# STC.net
KiCad netlist of a schematic drawn in Altium Designer
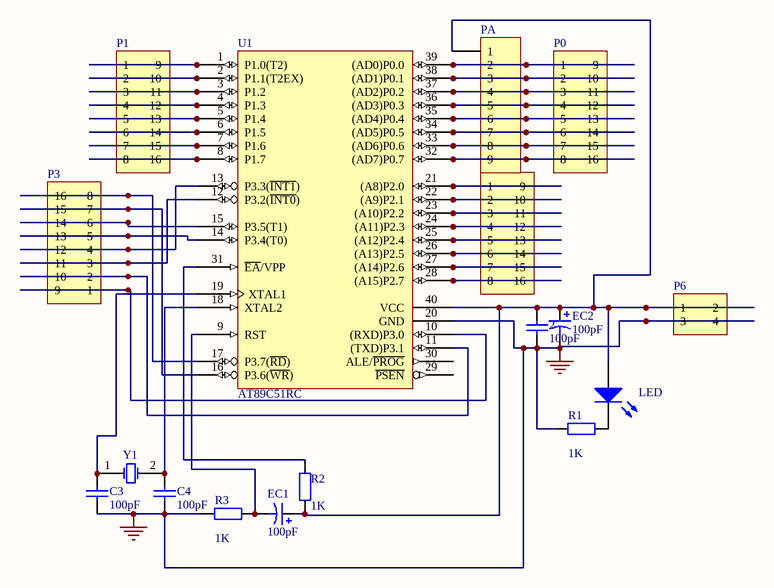
[diagram p0: STC最小系统板.SCHDOC]

(export (version "E")
  (design (tool "Eeschema 10.0.6"))
  (components
    (comp (ref "2")
      (value "100pF")
      (footprint "CAPR5-4X5")
      (description "Capacitor (Semiconductor SIM Model)")
      (fields (field (name "Comment") "Cap Semi") (field (name "PUBLISHER") "Altium Limited"))
      (libsource (lib "Miscellaneous Devices") (part "Cap Semi"))
    )
    (comp (ref "C3")
      (value "100pF")
      (footprint "CAPR5-4X5")
      (description "Capacitor (Semiconductor SIM Model)")
      (fields (field (name "Comment") "Cap Semi") (field (name "PUBLISHER") "Altium Limited"))
      (libsource (lib "Miscellaneous Devices") (part "Cap Semi"))
    )
    (comp (ref "C4")
      (value "100pF")
      (footprint "CAPR5-4X5")
      (description "Capacitor (Semiconductor SIM Model)")
      (fields (field (name "Comment") "Cap Semi") (field (name "PUBLISHER") "Altium Limited"))
      (libsource (lib "Miscellaneous Devices") (part "Cap Semi"))
    )
    (comp (ref "EC1")
      (value "100pF")
      (footprint "CAPPR1.5-4x5")
      (description "Polarized Capacitor (Radial)")
      (fields (field (name "Comment") "Cap Pol1") (field (name "PUBLISHER") "Altium Limited"))
      (libsource (lib "Miscellaneous Devices") (part "Cap Pol1"))
    )
    (comp (ref "EC2")
      (value "100pF")
      (footprint "CAPPR1.5-4x5")
      (description "Polarized Capacitor (Radial)")
      (fields (field (name "Comment") "Cap Pol1") (field (name "PUBLISHER") "Altium Limited"))
      (libsource (lib "Miscellaneous Devices") (part "Cap Pol1"))
    )
    (comp (ref "LED")
      (value "LED0")
      (footprint "CAPPR1.27-1.7x2.8")
      (description "Typical INFRARED GaAs LED")
      (fields (field (name "PUBLISHER") "Altium Limited"))
      (libsource (lib "Miscellaneous Devices") (part "LED0"))
    )
    (comp (ref "P0")
      (value "Header 8X2A")
      (footprint "HDR2X8_CEN")
      (description "Header, 8-Pin, Dual row")
      (fields (field (name "PUBLISHER") "Altium Limited"))
      (libsource (lib "Miscellaneous Connectors") (part "Header 8X2A"))
    )
    (comp (ref "P1")
      (value "Header 8X2A")
      (footprint "HDR2X8_CEN")
      (description "Header, 8-Pin, Dual row")
      (fields (field (name "PUBLISHER") "Altium Limited"))
      (libsource (lib "Miscellaneous Connectors") (part "Header 8X2A"))
    )
    (comp (ref "P2")
      (value "Header 8X2A")
      (footprint "HDR2X8_CEN")
      (description "Header, 8-Pin, Dual row")
      (fields (field (name "PUBLISHER") "Altium Limited"))
      (libsource (lib "Miscellaneous Connectors") (part "Header 8X2A"))
    )
    (comp (ref "P3")
      (value "Header 8X2A")
      (footprint "HDR2X8_CEN")
      (description "Header, 8-Pin, Dual row")
      (fields (field (name "PUBLISHER") "Altium Limited"))
      (libsource (lib "") (part "Header 8X2A_1"))
    )
    (comp (ref "P6")
      (value "MHDR2X2")
      (footprint "MHDR2X2")
      (description "Header, 2-Pin, Dual row")
      (fields (field (name "PUBLISHER") "Altium Limited"))
      (libsource (lib "Miscellaneous Connectors") (part "MHDR2X2"))
    )
    (comp (ref "PA")
      (value "Header 9")
      (footprint "HDR1X9")
      (description "Header, 9-Pin")
      (fields (field (name "PUBLISHER") "Altium Limited"))
      (libsource (lib "Miscellaneous Connectors") (part "Header 9"))
    )
    (comp (ref "R1")
      (value "1K")
      (footprint "AXIAL-0.4")
      (description "Resistor")
      (fields (field (name "Comment") "Res2") (field (name "PUBLISHER") "Altium Limited"))
      (libsource (lib "Miscellaneous Devices") (part "Res2"))
    )
    (comp (ref "R2")
      (value "1K")
      (footprint "AXIAL-0.4")
      (description "Resistor")
      (fields (field (name "Comment") "Res2") (field (name "PUBLISHER") "Altium Limited"))
      (libsource (lib "") (part "Res2_1"))
    )
    (comp (ref "R3")
      (value "1K")
      (footprint "AXIAL-0.4")
      (description "Resistor")
      (fields (field (name "Comment") "Res2") (field (name "PUBLISHER") "Altium Limited"))
      (libsource (lib "Miscellaneous Devices") (part "Res2"))
    )
    (comp (ref "U1")
      (value "AT89C51RC")
      (footprint "DIP-40")
      (description "8-Bit Microcontroller with 32K Flash ROM")
      (libsource (lib "Atmel Microcontroller 8051 Architecture") (part "AT89C51RC"))
    )
    (comp (ref "Y1")
      (value "XTAL")
      (footprint "RAD-0.2")
      (description "Crystal Oscillator")
      (fields (field (name "PUBLISHER") "Altium Limited"))
      (libsource (lib "Miscellaneous Devices") (part "XTAL"))
    )
  )
  (nets
    (net (code "1") (name "GND") (class "Default")
      (node (ref "2") (pin "1") (pinfunction "1_1") (pintype "passive"))
      (node (ref "C3") (pin "2") (pinfunction "2_2") (pintype "passive"))
      (node (ref "C4") (pin "2") (pinfunction "2_2") (pintype "passive"))
      (node (ref "EC2") (pin "2") (pinfunction "2_2") (pintype "passive"))
      (node (ref "P6") (pin "3") (pinfunction "3_3") (pintype "passive"))
      (node (ref "P6") (pin "4") (pinfunction "4_4") (pintype "passive"))
      (node (ref "R1") (pin "2") (pinfunction "2_2") (pintype "passive"))
      (node (ref "R3") (pin "2") (pinfunction "2_2") (pintype "passive"))
      (node (ref "U1") (pin "20") (pinfunction "GND_20") (pintype "power_in"))
    )
    (net (code "2") (name "Net-(LED-A)") (class "Default")
      (node (ref "2") (pin "2") (pinfunction "2_2") (pintype "passive"))
      (node (ref "EC1") (pin "1") (pinfunction "1_1") (pintype "passive"))
      (node (ref "EC2") (pin "1") (pinfunction "1_1") (pintype "passive"))
      (node (ref "LED") (pin "1") (pinfunction "A_1") (pintype "passive"))
      (node (ref "P6") (pin "1") (pinfunction "1_1") (pintype "passive"))
      (node (ref "P6") (pin "2") (pinfunction "2_2") (pintype "passive"))
      (node (ref "PA") (pin "1") (pinfunction "1_1") (pintype "passive"))
      (node (ref "R2") (pin "2") (pinfunction "2_2") (pintype "passive"))
      (node (ref "U1") (pin "40") (pinfunction "VCC_40") (pintype "power_in"))
    )
    (net (code "3") (name "Net-(LED-K)") (class "Default")
      (node (ref "LED") (pin "2") (pinfunction "K_2") (pintype "passive"))
      (node (ref "R1") (pin "1") (pinfunction "1_1") (pintype "passive"))
    )
    (net (code "4") (name "Net-(U1-(A8)P2.0)") (class "Default")
      (node (ref "P2") (pin "1") (pinfunction "1_1") (pintype "passive"))
      (node (ref "P2") (pin "9") (pinfunction "9_9") (pintype "passive"))
      (node (ref "U1") (pin "21") (pinfunction "(A8)P2.0_21") (pintype "bidirectional"))
    )
    (net (code "5") (name "Net-(U1-(A9)P2.1)") (class "Default")
      (node (ref "P2") (pin "10") (pinfunction "10_10") (pintype "passive"))
      (node (ref "P2") (pin "2") (pinfunction "2_2") (pintype "passive"))
      (node (ref "U1") (pin "22") (pinfunction "(A9)P2.1_22") (pintype "bidirectional"))
    )
    (net (code "6") (name "Net-(U1-(A10)P2.2)") (class "Default")
      (node (ref "P2") (pin "11") (pinfunction "11_11") (pintype "passive"))
      (node (ref "P2") (pin "3") (pinfunction "3_3") (pintype "passive"))
      (node (ref "U1") (pin "23") (pinfunction "(A10)P2.2_23") (pintype "bidirectional"))
    )
    (net (code "7") (name "Net-(U1-(A11)P2.3)") (class "Default")
      (node (ref "P2") (pin "12") (pinfunction "12_12") (pintype "passive"))
      (node (ref "P2") (pin "4") (pinfunction "4_4") (pintype "passive"))
      (node (ref "U1") (pin "24") (pinfunction "(A11)P2.3_24") (pintype "bidirectional"))
    )
    (net (code "8") (name "Net-(U1-(A12)P2.4)") (class "Default")
      (node (ref "P2") (pin "13") (pinfunction "13_13") (pintype "passive"))
      (node (ref "P2") (pin "5") (pinfunction "5_5") (pintype "passive"))
      (node (ref "U1") (pin "25") (pinfunction "(A12)P2.4_25") (pintype "bidirectional"))
    )
    (net (code "9") (name "Net-(U1-(A13)P2.5)") (class "Default")
      (node (ref "P2") (pin "14") (pinfunction "14_14") (pintype "passive"))
      (node (ref "P2") (pin "6") (pinfunction "6_6") (pintype "passive"))
      (node (ref "U1") (pin "26") (pinfunction "(A13)P2.5_26") (pintype "bidirectional"))
    )
    (net (code "10") (name "Net-(U1-(A14)P2.6)") (class "Default")
      (node (ref "P2") (pin "15") (pinfunction "15_15") (pintype "passive"))
      (node (ref "P2") (pin "7") (pinfunction "7_7") (pintype "passive"))
      (node (ref "U1") (pin "27") (pinfunction "(A14)P2.6_27") (pintype "bidirectional"))
    )
    (net (code "11") (name "Net-(U1-(A15)P2.7)") (class "Default")
      (node (ref "P2") (pin "16") (pinfunction "16_16") (pintype "passive"))
      (node (ref "P2") (pin "8") (pinfunction "8_8") (pintype "passive"))
      (node (ref "U1") (pin "28") (pinfunction "(A15)P2.7_28") (pintype "bidirectional"))
    )
    (net (code "12") (name "Net-(U1-(AD0)P0.0)") (class "Default")
      (node (ref "P0") (pin "1") (pinfunction "1_1") (pintype "passive"))
      (node (ref "P0") (pin "9") (pinfunction "9_9") (pintype "passive"))
      (node (ref "PA") (pin "2") (pinfunction "2_2") (pintype "passive"))
      (node (ref "U1") (pin "39") (pinfunction "(AD0)P0.0_39") (pintype "bidirectional"))
    )
    (net (code "13") (name "Net-(U1-(AD1)P0.1)") (class "Default")
      (node (ref "P0") (pin "10") (pinfunction "10_10") (pintype "passive"))
      (node (ref "P0") (pin "2") (pinfunction "2_2") (pintype "passive"))
      (node (ref "PA") (pin "3") (pinfunction "3_3") (pintype "passive"))
      (node (ref "U1") (pin "38") (pinfunction "(AD1)P0.1_38") (pintype "bidirectional"))
    )
    (net (code "14") (name "Net-(U1-(AD2)P0.2)") (class "Default")
      (node (ref "P0") (pin "11") (pinfunction "11_11") (pintype "passive"))
      (node (ref "P0") (pin "3") (pinfunction "3_3") (pintype "passive"))
      (node (ref "PA") (pin "4") (pinfunction "4_4") (pintype "passive"))
      (node (ref "U1") (pin "37") (pinfunction "(AD2)P0.2_37") (pintype "bidirectional"))
    )
    (net (code "15") (name "Net-(U1-(AD3)P0.3)") (class "Default")
      (node (ref "P0") (pin "12") (pinfunction "12_12") (pintype "passive"))
      (node (ref "P0") (pin "4") (pinfunction "4_4") (pintype "passive"))
      (node (ref "PA") (pin "5") (pinfunction "5_5") (pintype "passive"))
      (node (ref "U1") (pin "36") (pinfunction "(AD3)P0.3_36") (pintype "bidirectional"))
    )
    (net (code "16") (name "Net-(U1-(AD4)P0.4)") (class "Default")
      (node (ref "P0") (pin "13") (pinfunction "13_13") (pintype "passive"))
      (node (ref "P0") (pin "5") (pinfunction "5_5") (pintype "passive"))
      (node (ref "PA") (pin "6") (pinfunction "6_6") (pintype "passive"))
      (node (ref "U1") (pin "35") (pinfunction "(AD4)P0.4_35") (pintype "bidirectional"))
    )
    (net (code "17") (name "Net-(U1-(AD5)P0.5)") (class "Default")
      (node (ref "P0") (pin "14") (pinfunction "14_14") (pintype "passive"))
      (node (ref "P0") (pin "6") (pinfunction "6_6") (pintype "passive"))
      (node (ref "PA") (pin "7") (pinfunction "7_7") (pintype "passive"))
      (node (ref "U1") (pin "34") (pinfunction "(AD5)P0.5_34") (pintype "bidirectional"))
    )
    (net (code "18") (name "Net-(U1-(AD6)P0.6)") (class "Default")
      (node (ref "P0") (pin "15") (pinfunction "15_15") (pintype "passive"))
      (node (ref "P0") (pin "7") (pinfunction "7_7") (pintype "passive"))
      (node (ref "PA") (pin "8") (pinfunction "8_8") (pintype "passive"))
      (node (ref "U1") (pin "33") (pinfunction "(AD6)P0.6_33") (pintype "bidirectional"))
    )
    (net (code "19") (name "Net-(U1-(AD7)P0.7)") (class "Default")
      (node (ref "P0") (pin "16") (pinfunction "16_16") (pintype "passive"))
      (node (ref "P0") (pin "8") (pinfunction "8_8") (pintype "passive"))
      (node (ref "PA") (pin "9") (pinfunction "9_9") (pintype "passive"))
      (node (ref "U1") (pin "32") (pinfunction "(AD7)P0.7_32") (pintype "bidirectional"))
    )
    (net (code "20") (name "Net-(U1-(RXD)P3.0)") (class "Default")
      (node (ref "P3") (pin "1") (pinfunction "1_1") (pintype "passive"))
      (node (ref "P3") (pin "9") (pinfunction "9_9") (pintype "passive"))
      (node (ref "U1") (pin "10") (pinfunction "(RXD)P3.0_10") (pintype "bidirectional"))
    )
    (net (code "21") (name "Net-(U1-(TXD)P3.1)") (class "Default")
      (node (ref "P3") (pin "10") (pinfunction "10_10") (pintype "passive"))
      (node (ref "P3") (pin "2") (pinfunction "2_2") (pintype "passive"))
      (node (ref "U1") (pin "11") (pinfunction "(TXD)P3.1_11") (pintype "bidirectional"))
    )
    (net (code "22") (name "Net-(U1-P1.0(T2))") (class "Default")
      (node (ref "P1") (pin "1") (pinfunction "1_1") (pintype "passive"))
      (node (ref "P1") (pin "9") (pinfunction "9_9") (pintype "passive"))
      (node (ref "U1") (pin "1") (pinfunction "P1.0(T2)_1") (pintype "bidirectional"))
    )
    (net (code "23") (name "Net-(U1-P1.1(T2EX))") (class "Default")
      (node (ref "P1") (pin "10") (pinfunction "10_10") (pintype "passive"))
      (node (ref "P1") (pin "2") (pinfunction "2_2") (pintype "passive"))
      (node (ref "U1") (pin "2") (pinfunction "P1.1(T2EX)_2") (pintype "bidirectional"))
    )
    (net (code "24") (name "Net-(U1-P1.2)") (class "Default")
      (node (ref "P1") (pin "11") (pinfunction "11_11") (pintype "passive"))
      (node (ref "P1") (pin "3") (pinfunction "3_3") (pintype "passive"))
      (node (ref "U1") (pin "3") (pinfunction "P1.2_3") (pintype "bidirectional"))
    )
    (net (code "25") (name "Net-(U1-P1.3)") (class "Default")
      (node (ref "P1") (pin "12") (pinfunction "12_12") (pintype "passive"))
      (node (ref "P1") (pin "4") (pinfunction "4_4") (pintype "passive"))
      (node (ref "U1") (pin "4") (pinfunction "P1.3_4") (pintype "bidirectional"))
    )
    (net (code "26") (name "Net-(U1-P1.4)") (class "Default")
      (node (ref "P1") (pin "13") (pinfunction "13_13") (pintype "passive"))
      (node (ref "P1") (pin "5") (pinfunction "5_5") (pintype "passive"))
      (node (ref "U1") (pin "5") (pinfunction "P1.4_5") (pintype "bidirectional"))
    )
    (net (code "27") (name "Net-(U1-P1.5)") (class "Default")
      (node (ref "P1") (pin "14") (pinfunction "14_14") (pintype "passive"))
      (node (ref "P1") (pin "6") (pinfunction "6_6") (pintype "passive"))
      (node (ref "U1") (pin "6") (pinfunction "P1.5_6") (pintype "bidirectional"))
    )
    (net (code "28") (name "Net-(U1-P1.6)") (class "Default")
      (node (ref "P1") (pin "15") (pinfunction "15_15") (pintype "passive"))
      (node (ref "P1") (pin "7") (pinfunction "7_7") (pintype "passive"))
      (node (ref "U1") (pin "7") (pinfunction "P1.6_7") (pintype "bidirectional"))
    )
    (net (code "29") (name "Net-(U1-P1.7)") (class "Default")
      (node (ref "P1") (pin "16") (pinfunction "16_16") (pintype "passive"))
      (node (ref "P1") (pin "8") (pinfunction "8_8") (pintype "passive"))
      (node (ref "U1") (pin "8") (pinfunction "P1.7_8") (pintype "bidirectional"))
    )
    (net (code "30") (name "Net-(U1-P3.2(~{INT0}))") (class "Default")
      (node (ref "P3") (pin "11") (pinfunction "11_11") (pintype "passive"))
      (node (ref "P3") (pin "3") (pinfunction "3_3") (pintype "passive"))
      (node (ref "U1") (pin "12") (pinfunction "P3.2(~{INT0})_12") (pintype "bidirectional"))
    )
    (net (code "31") (name "Net-(U1-P3.3(~{INT1}))") (class "Default")
      (node (ref "P3") (pin "12") (pinfunction "12_12") (pintype "passive"))
      (node (ref "P3") (pin "4") (pinfunction "4_4") (pintype "passive"))
      (node (ref "U1") (pin "13") (pinfunction "P3.3(~{INT1})_13") (pintype "bidirectional"))
    )
    (net (code "32") (name "Net-(U1-P3.4(T0))") (class "Default")
      (node (ref "P3") (pin "13") (pinfunction "13_13") (pintype "passive"))
      (node (ref "P3") (pin "5") (pinfunction "5_5") (pintype "passive"))
      (node (ref "U1") (pin "14") (pinfunction "P3.4(T0)_14") (pintype "bidirectional"))
    )
    (net (code "33") (name "Net-(U1-P3.5(T1))") (class "Default")
      (node (ref "P3") (pin "14") (pinfunction "14_14") (pintype "passive"))
      (node (ref "P3") (pin "6") (pinfunction "6_6") (pintype "passive"))
      (node (ref "U1") (pin "15") (pinfunction "P3.5(T1)_15") (pintype "bidirectional"))
    )
    (net (code "34") (name "Net-(U1-P3.6(~{WR}))") (class "Default")
      (node (ref "P3") (pin "15") (pinfunction "15_15") (pintype "passive"))
      (node (ref "P3") (pin "7") (pinfunction "7_7") (pintype "passive"))
      (node (ref "U1") (pin "16") (pinfunction "P3.6(~{WR})_16") (pintype "bidirectional"))
    )
    (net (code "35") (name "Net-(U1-P3.7(~{RD}))") (class "Default")
      (node (ref "P3") (pin "16") (pinfunction "16_16") (pintype "passive"))
      (node (ref "P3") (pin "8") (pinfunction "8_8") (pintype "passive"))
      (node (ref "U1") (pin "17") (pinfunction "P3.7(~{RD})_17") (pintype "bidirectional"))
    )
    (net (code "36") (name "Net-(U1-RST)") (class "Default")
      (node (ref "EC1") (pin "2") (pinfunction "2_2") (pintype "passive"))
      (node (ref "R3") (pin "1") (pinfunction "1_1") (pintype "passive"))
      (node (ref "U1") (pin "9") (pinfunction "RST_9") (pintype "input"))
    )
    (net (code "37") (name "Net-(U1-XTAL1)") (class "Default")
      (node (ref "C3") (pin "1") (pinfunction "1_1") (pintype "passive"))
      (node (ref "U1") (pin "19") (pinfunction "XTAL1_19") (pintype "input"))
      (node (ref "Y1") (pin "1") (pinfunction "OSC1_1") (pintype "passive"))
    )
    (net (code "38") (name "Net-(U1-XTAL2)") (class "Default")
      (node (ref "C4") (pin "1") (pinfunction "1_1") (pintype "passive"))
      (node (ref "U1") (pin "18") (pinfunction "XTAL2_18") (pintype "input"))
      (node (ref "Y1") (pin "2") (pinfunction "OSC2_2") (pintype "passive"))
    )
    (net (code "39") (name "Net-(U1-~{EA}{slash}VPP)") (class "Default")
      (node (ref "R2") (pin "1") (pinfunction "1_1") (pintype "passive"))
      (node (ref "U1") (pin "31") (pinfunction "~{EA}/VPP_31") (pintype "input"))
    )
    (net (code "40") (name "unconnected-(U1-ALE{slash}~{PROG}-Pad30)") (class "Default")
      (node (ref "U1") (pin "30") (pinfunction "ALE/~{PROG}_30") (pintype "output"))
    )
    (net (code "41") (name "unconnected-(U1-~{PSEN}-Pad29)") (class "Default")
      (node (ref "U1") (pin "29") (pinfunction "~{PSEN}_29") (pintype "output"))
    )
  )
)
